# 1_87.net
KiCad netlist of a schematic drawn in EasyEDA Pro
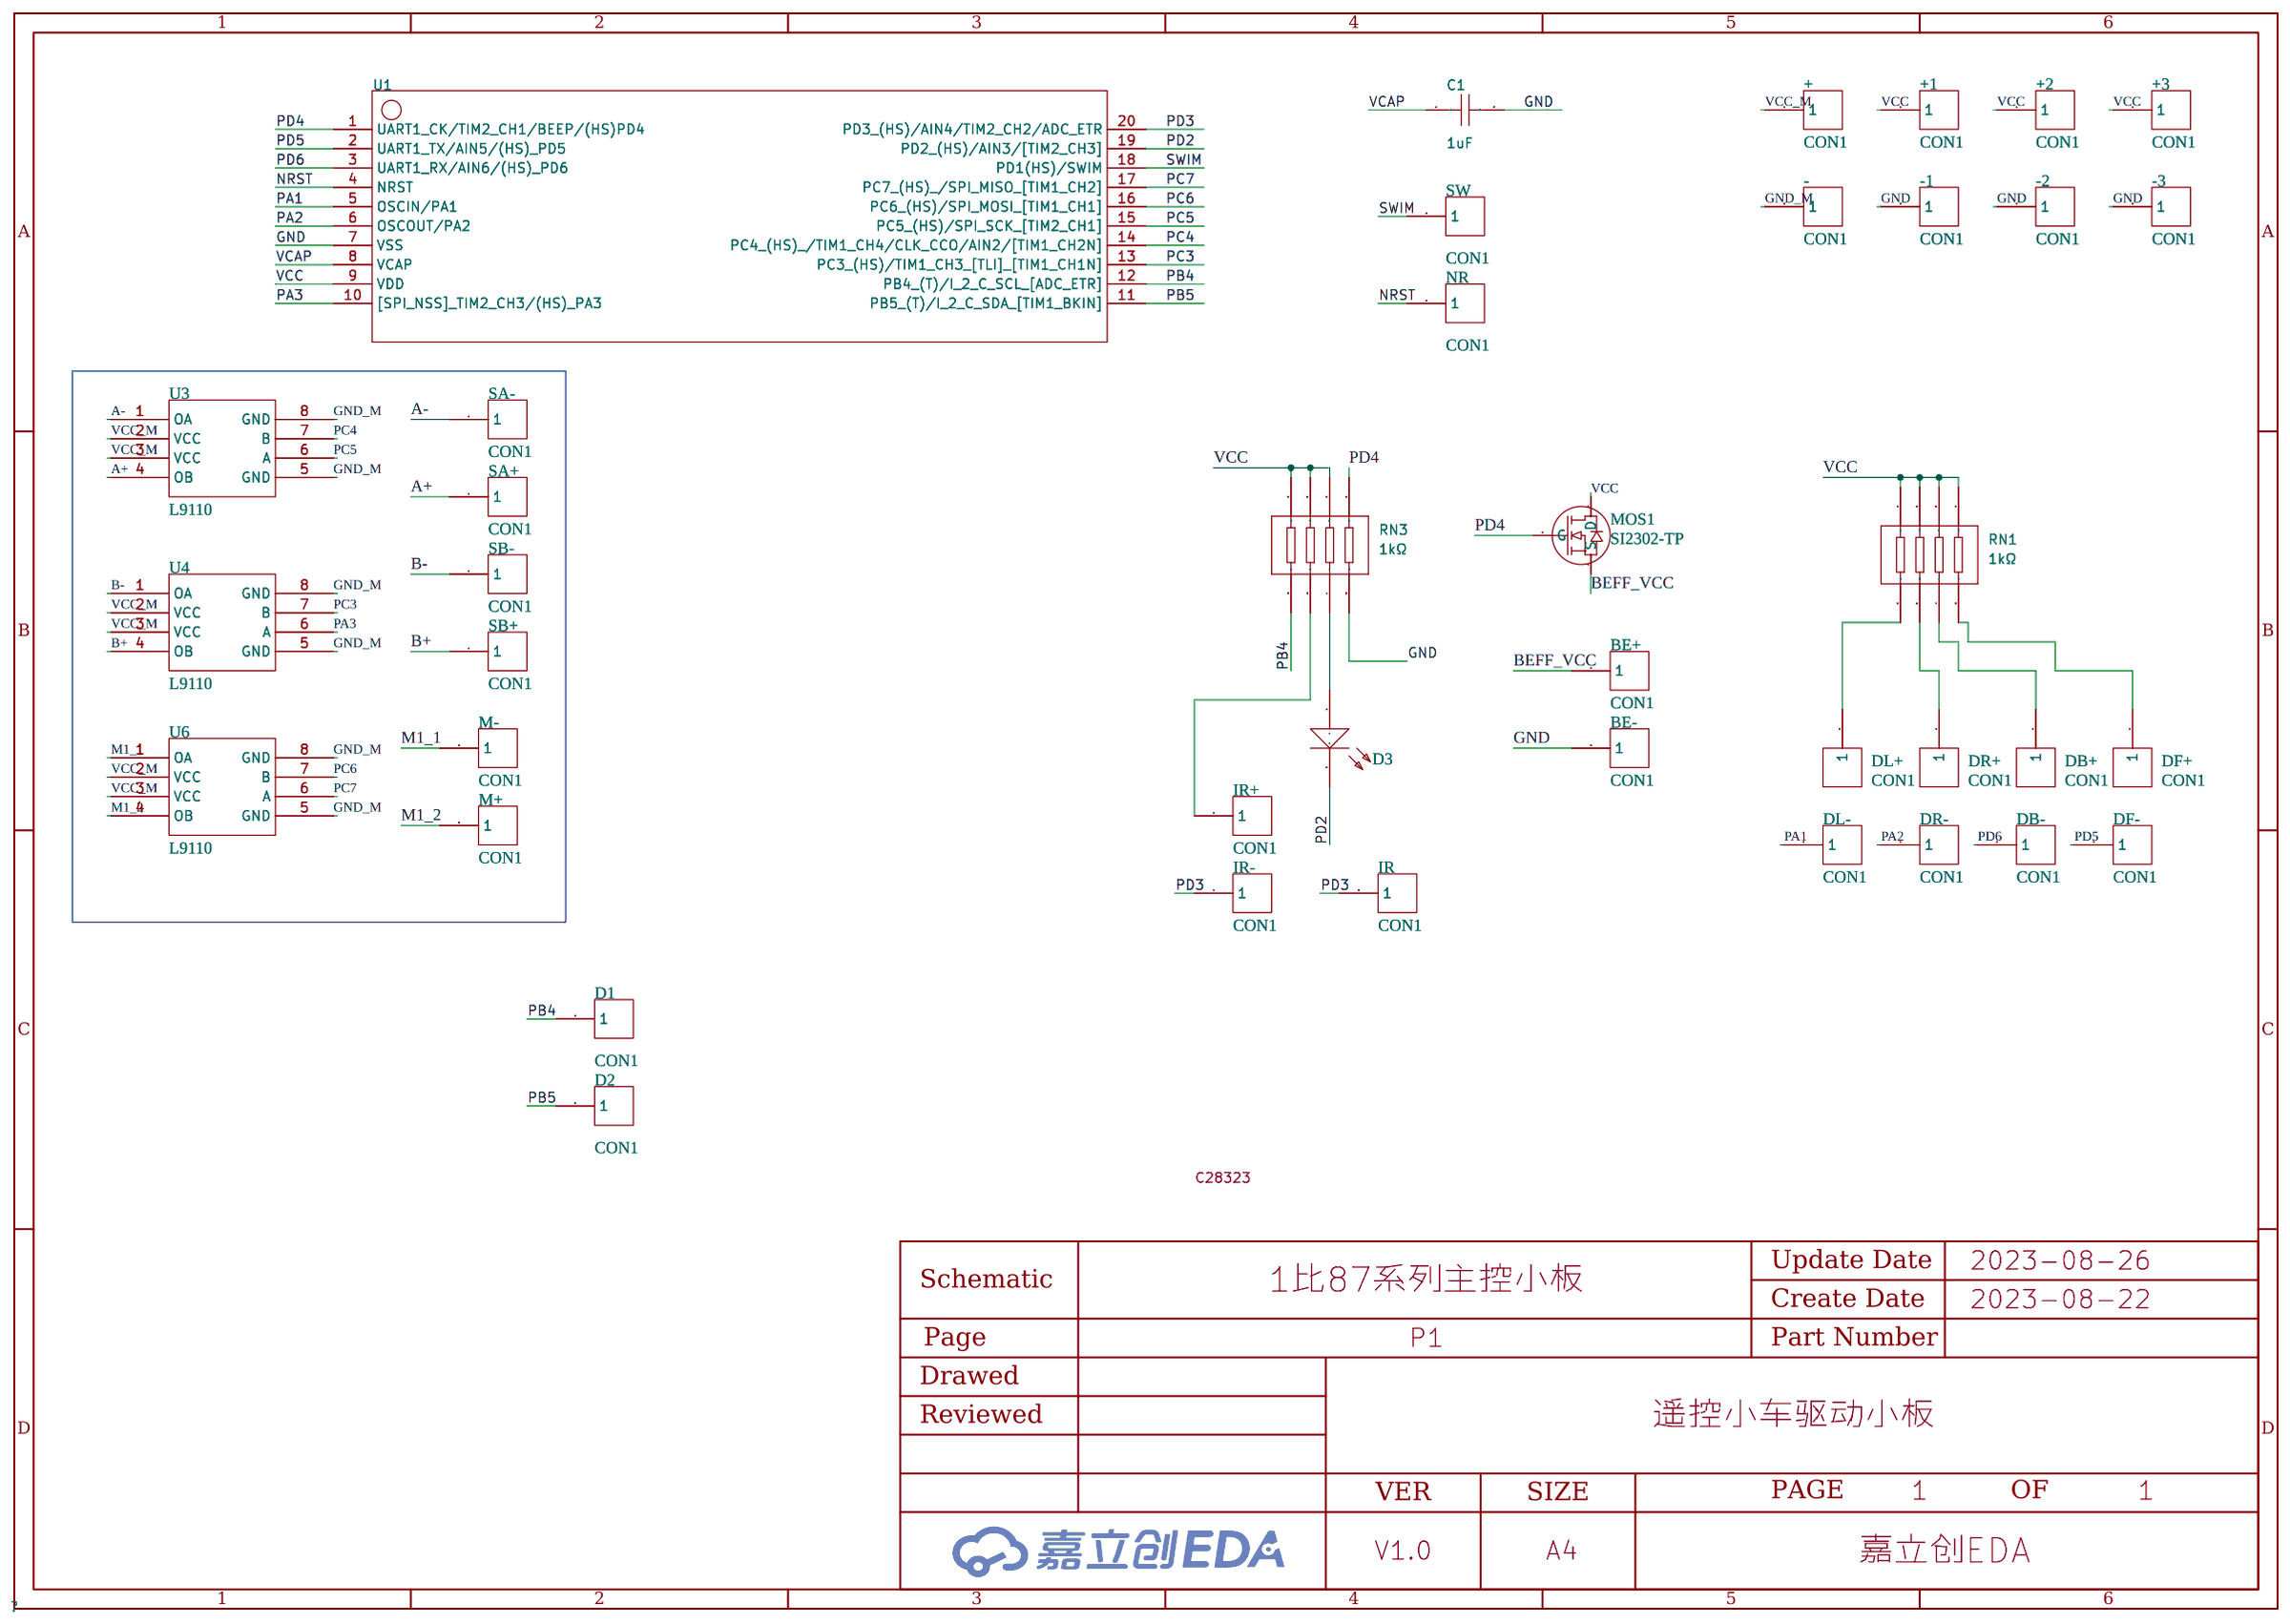
[diagram p0: schematic sheet]

(export (version "E")
  (design (tool "Eeschema 10.0.6"))
  (components
    (comp (ref "+")
      (value "CON1")
      (footprint "easyedapro:CON1_2")
      (libsource (lib "easyedapro") (part "CON1"))
    )
    (comp (ref "+1")
      (value "CON1")
      (footprint "easyedapro:CON1_2")
      (libsource (lib "easyedapro") (part "CON1"))
    )
    (comp (ref "+2")
      (value "CON1")
      (footprint "easyedapro:CON1_2")
      (libsource (lib "easyedapro") (part "CON1"))
    )
    (comp (ref "+3")
      (value "CON1")
      (footprint "easyedapro:CON1_2")
      (libsource (lib "easyedapro") (part "CON1"))
    )
    (comp (ref "-")
      (value "CON1")
      (footprint "easyedapro:CON1_2")
      (libsource (lib "easyedapro") (part "CON1"))
    )
    (comp (ref "-1")
      (value "CON1")
      (footprint "easyedapro:CON1_2")
      (libsource (lib "easyedapro") (part "CON1"))
    )
    (comp (ref "-2")
      (value "CON1")
      (footprint "easyedapro:CON1_2")
      (libsource (lib "easyedapro") (part "CON1"))
    )
    (comp (ref "-3")
      (value "CON1")
      (footprint "easyedapro:CON1_2")
      (libsource (lib "easyedapro") (part "CON1"))
    )
    (comp (ref "BE+")
      (value "CON1")
      (footprint "easyedapro:CON1_2")
      (libsource (lib "easyedapro") (part "CON1"))
    )
    (comp (ref "BE-")
      (value "CON1")
      (footprint "easyedapro:CON1_2")
      (libsource (lib "easyedapro") (part "CON1"))
    )
    (comp (ref "C1")
      (value "1uF")
      (fields
        (field (name "Manufacturer Part") "CL21B105KBFNNNE")
        (field (name "Manufacturer") "SAMSUNG(三星)")
        (field (name "Supplier Part") "C28323")
      )
      (libsource (lib "easyedapro") (part "CapAcitance"))
    )
    (comp (ref "D1")
      (value "CON1")
      (footprint "easyedapro:CON1_2")
      (libsource (lib "easyedapro") (part "CON1"))
    )
    (comp (ref "D2")
      (value "CON1")
      (footprint "easyedapro:CON1_2")
      (libsource (lib "easyedapro") (part "CON1"))
    )
    (comp (ref "D3")
      (value "LED0")
      (footprint "easyedapro:LED-0805")
      (description "发光二极管")
      (fields (field (name "Publisher") "Altium Limited"))
      (libsource (lib "easyedapro") (part "LED0"))
    )
    (comp (ref "DB+")
      (value "CON1")
      (footprint "easyedapro:CON1_2")
      (libsource (lib "easyedapro") (part "CON1"))
    )
    (comp (ref "DB-")
      (value "CON1")
      (footprint "easyedapro:CON1_2")
      (libsource (lib "easyedapro") (part "CON1"))
    )
    (comp (ref "DF+")
      (value "CON1")
      (footprint "easyedapro:CON1_2")
      (libsource (lib "easyedapro") (part "CON1"))
    )
    (comp (ref "DF-")
      (value "CON1")
      (footprint "easyedapro:CON1_2")
      (libsource (lib "easyedapro") (part "CON1"))
    )
    (comp (ref "DL+")
      (value "CON1")
      (footprint "easyedapro:CON1_2")
      (libsource (lib "easyedapro") (part "CON1"))
    )
    (comp (ref "DL-")
      (value "CON1")
      (footprint "easyedapro:CON1_2")
      (libsource (lib "easyedapro") (part "CON1"))
    )
    (comp (ref "DR+")
      (value "CON1")
      (footprint "easyedapro:CON1_2")
      (libsource (lib "easyedapro") (part "CON1"))
    )
    (comp (ref "DR-")
      (value "CON1")
      (footprint "easyedapro:CON1_2")
      (libsource (lib "easyedapro") (part "CON1"))
    )
    (comp (ref "IR")
      (value "CON1")
      (footprint "easyedapro:CON1_2")
      (libsource (lib "easyedapro") (part "CON1"))
    )
    (comp (ref "IR+")
      (value "CON1")
      (footprint "easyedapro:CON1_2")
      (libsource (lib "easyedapro") (part "CON1"))
    )
    (comp (ref "IR-")
      (value "CON1")
      (footprint "easyedapro:CON1_2")
      (libsource (lib "easyedapro") (part "CON1"))
    )
    (comp (ref "M+")
      (value "CON1")
      (footprint "easyedapro:CON1_2")
      (libsource (lib "easyedapro") (part "CON1"))
    )
    (comp (ref "M-")
      (value "CON1")
      (footprint "easyedapro:CON1_2")
      (libsource (lib "easyedapro") (part "CON1"))
    )
    (comp (ref "MOS1")
      (value "SI2302-TP")
      (footprint "easyedapro:SOT-23_MCC")
      (description "No Description Available")
      (fields (field (name "Copyright") "Copyright (C) 2022 Ultra Librarian. All rights reserved."))
      (libsource (lib "easyedapro") (part "SI2302-TP"))
    )
    (comp (ref "NR")
      (value "CON1")
      (footprint "easyedapro:CON1_2")
      (libsource (lib "easyedapro") (part "CON1"))
    )
    (comp (ref "RN1")
      (value "1kΩ")
      (footprint "easyedapro:RES-ARRAY-SMD_0603-8P-L3.2-W1.6-BL")
      (description "阻值:1kΩ;精度:±5%;单个元件功率:62.5mW;电阻器数:4;")
      (fields
        (field (name "Manufacturer Part") "4D03WGJ0102T5E")
        (field (name "Manufacturer") "UNI-ROYAL(厚声)")
      )
      (libsource (lib "easyedapro") (part "4D03WGJ0102T5E"))
    )
    (comp (ref "RN3")
      (value "1kΩ")
      (footprint "easyedapro:RES-ARRAY-SMD_0603-8P-L3.2-W1.6-BL")
      (description "阻值:1kΩ;精度:±5%;单个元件功率:62.5mW;电阻器数:4;")
      (fields
        (field (name "Manufacturer Part") "4D03WGJ0102T5E")
        (field (name "Manufacturer") "UNI-ROYAL(厚声)")
      )
      (libsource (lib "easyedapro") (part "4D03WGJ0102T5E"))
    )
    (comp (ref "SA+")
      (value "CON1")
      (footprint "easyedapro:CON1_2")
      (libsource (lib "easyedapro") (part "CON1"))
    )
    (comp (ref "SA-")
      (value "CON1")
      (footprint "easyedapro:CON1_2")
      (libsource (lib "easyedapro") (part "CON1"))
    )
    (comp (ref "SB+")
      (value "CON1")
      (footprint "easyedapro:CON1_2")
      (libsource (lib "easyedapro") (part "CON1"))
    )
    (comp (ref "SB-")
      (value "CON1")
      (footprint "easyedapro:CON1_2")
      (libsource (lib "easyedapro") (part "CON1"))
    )
    (comp (ref "SW")
      (value "CON1")
      (footprint "easyedapro:CON1_2")
      (libsource (lib "easyedapro") (part "CON1"))
    )
    (comp (ref "U1")
      (value "STM8S003F3P6")
      (footprint "easyedapro:TSSOP-20_L6.5-W4.4-P0.65-LS6.4-BL")
      (description "CPU内核:STM8;CPU最大主频:16MHz;程序存储容量:8KB;程序存储器类型:FLASH;RAM总容量:1KB;GPIO端口数量:16;")
      (fields (field (name "Manufacturer") "ST(意法半导体)"))
      (libsource (lib "easyedapro") (part "STM8S003F3P6"))
    )
    (comp (ref "U3")
      (value "L9110")
      (footprint "easyedapro:SOP8")
      (libsource (lib "easyedapro") (part "L9110"))
    )
    (comp (ref "U4")
      (value "L9110")
      (footprint "easyedapro:SOP8")
      (libsource (lib "easyedapro") (part "L9110"))
    )
    (comp (ref "U6")
      (value "L9110")
      (footprint "easyedapro:SOP8")
      (libsource (lib "easyedapro") (part "L9110"))
    )
  )
  (nets
    (net (code "1") (name "/A+") (class "Default")
      (node (ref "SA+") (pin "1") (pinfunction "1_1") (pintype "input"))
      (node (ref "U3") (pin "4") (pinfunction "OB_4") (pintype "input"))
    )
    (net (code "2") (name "/A-") (class "Default")
      (node (ref "SA-") (pin "1") (pinfunction "1_1") (pintype "input"))
      (node (ref "U3") (pin "1") (pinfunction "OA_1") (pintype "input"))
    )
    (net (code "3") (name "/B+") (class "Default")
      (node (ref "SB+") (pin "1") (pinfunction "1_1") (pintype "input"))
      (node (ref "U4") (pin "4") (pinfunction "OB_4") (pintype "input"))
    )
    (net (code "4") (name "/B-") (class "Default")
      (node (ref "SB-") (pin "1") (pinfunction "1_1") (pintype "input"))
      (node (ref "U4") (pin "1") (pinfunction "OA_1") (pintype "input"))
    )
    (net (code "5") (name "/BEFF_VCC") (class "Default")
      (node (ref "BE+") (pin "1") (pinfunction "1_1") (pintype "input"))
      (node (ref "MOS1") (pin "2") (pinfunction "S_2") (pintype "input"))
    )
    (net (code "6") (name "/GND") (class "Default")
      (node (ref "-1") (pin "1") (pinfunction "1_1") (pintype "input"))
      (node (ref "-2") (pin "1") (pinfunction "1_1") (pintype "input"))
      (node (ref "-3") (pin "1") (pinfunction "1_1") (pintype "input"))
      (node (ref "BE-") (pin "1") (pinfunction "1_1") (pintype "input"))
      (node (ref "C1") (pin "2") (pinfunction "2_2") (pintype "input"))
      (node (ref "RN3") (pin "8") (pinfunction "8_8") (pintype "input"))
      (node (ref "U1") (pin "7") (pinfunction "VSS_7") (pintype "input"))
    )
    (net (code "7") (name "/GND_M") (class "Default")
      (node (ref "-") (pin "1") (pinfunction "1_1") (pintype "input"))
      (node (ref "U3") (pin "5") (pinfunction "GND_5") (pintype "input"))
      (node (ref "U3") (pin "8") (pinfunction "GND_8") (pintype "input"))
      (node (ref "U4") (pin "5") (pinfunction "GND_5") (pintype "input"))
      (node (ref "U4") (pin "8") (pinfunction "GND_8") (pintype "input"))
      (node (ref "U6") (pin "5") (pinfunction "GND_5") (pintype "input"))
      (node (ref "U6") (pin "8") (pinfunction "GND_8") (pintype "input"))
    )
    (net (code "8") (name "/M1_1") (class "Default")
      (node (ref "M-") (pin "1") (pinfunction "1_1") (pintype "input"))
      (node (ref "U6") (pin "1") (pinfunction "OA_1") (pintype "input"))
    )
    (net (code "9") (name "/M1_2") (class "Default")
      (node (ref "M+") (pin "1") (pinfunction "1_1") (pintype "input"))
      (node (ref "U6") (pin "4") (pinfunction "OB_4") (pintype "input"))
    )
    (net (code "10") (name "/NRST") (class "Default")
      (node (ref "NR") (pin "1") (pinfunction "1_1") (pintype "input"))
      (node (ref "U1") (pin "4") (pinfunction "NRST_4") (pintype "input"))
    )
    (net (code "11") (name "/PA1") (class "Default")
      (node (ref "DL-") (pin "1") (pinfunction "1_1") (pintype "input"))
      (node (ref "U1") (pin "5") (pinfunction "OSCIN/PA1_5") (pintype "input"))
    )
    (net (code "12") (name "/PA2") (class "Default")
      (node (ref "DR-") (pin "1") (pinfunction "1_1") (pintype "input"))
      (node (ref "U1") (pin "6") (pinfunction "OSCOUT/PA2_6") (pintype "input"))
    )
    (net (code "13") (name "/PA3") (class "Default")
      (node (ref "U1") (pin "10") (pinfunction "[SPI_NSS]_TIM2_CH3/(HS)_PA3_10") (pintype "input"))
      (node (ref "U4") (pin "6") (pinfunction "A_6") (pintype "input"))
    )
    (net (code "14") (name "/PB4") (class "Default")
      (node (ref "D1") (pin "1") (pinfunction "1_1") (pintype "input"))
      (node (ref "RN3") (pin "5") (pinfunction "5_5") (pintype "input"))
      (node (ref "U1") (pin "12") (pinfunction "PB4_(T)/I_2_C_SCL_[ADC_ETR]_12") (pintype "input"))
    )
    (net (code "15") (name "/PB5") (class "Default")
      (node (ref "D2") (pin "1") (pinfunction "1_1") (pintype "input"))
      (node (ref "U1") (pin "11") (pinfunction "PB5_(T)/I_2_C_SDA_[TIM1_BKIN]_11") (pintype "input"))
    )
    (net (code "16") (name "/PC3") (class "Default")
      (node (ref "U1") (pin "13") (pinfunction "PC3_(HS)/TIM1_CH3_[TLI]_[TIM1_CH1N]_13") (pintype "input"))
      (node (ref "U4") (pin "7") (pinfunction "B_7") (pintype "input"))
    )
    (net (code "17") (name "/PC4") (class "Default")
      (node (ref "U1") (pin "14") (pinfunction "PC4_(HS)_/TIM1_CH4/CLK_CCO/AIN2/[TIM1_CH2N]_14") (pintype "input"))
      (node (ref "U3") (pin "7") (pinfunction "B_7") (pintype "input"))
    )
    (net (code "18") (name "/PC5") (class "Default")
      (node (ref "U1") (pin "15") (pinfunction "PC5_(HS)/SPI_SCK_[TIM2_CH1]_15") (pintype "input"))
      (node (ref "U3") (pin "6") (pinfunction "A_6") (pintype "input"))
    )
    (net (code "19") (name "/PC6") (class "Default")
      (node (ref "U1") (pin "16") (pinfunction "PC6_(HS)/SPI_MOSI_[TIM1_CH1]_16") (pintype "input"))
      (node (ref "U6") (pin "7") (pinfunction "B_7") (pintype "input"))
    )
    (net (code "20") (name "/PC7") (class "Default")
      (node (ref "U1") (pin "17") (pinfunction "PC7_(HS)_/SPI_MISO_[TIM1_CH2]_17") (pintype "input"))
      (node (ref "U6") (pin "6") (pinfunction "A_6") (pintype "input"))
    )
    (net (code "21") (name "/PD2") (class "Default")
      (node (ref "D3") (pin "2") (pinfunction "K_2") (pintype "input"))
      (node (ref "U1") (pin "19") (pinfunction "PD2_(HS)/AIN3/[TIM2_CH3]_19") (pintype "input"))
    )
    (net (code "22") (name "/PD3") (class "Default")
      (node (ref "IR") (pin "1") (pinfunction "1_1") (pintype "input"))
      (node (ref "IR-") (pin "1") (pinfunction "1_1") (pintype "input"))
      (node (ref "U1") (pin "20") (pinfunction "PD3_(HS)/AIN4/TIM2_CH2/ADC_ETR_20") (pintype "input"))
    )
    (net (code "23") (name "/PD4") (class "Default")
      (node (ref "MOS1") (pin "1") (pinfunction "G_1") (pintype "input"))
      (node (ref "RN3") (pin "1") (pinfunction "1_1") (pintype "input"))
      (node (ref "U1") (pin "1") (pinfunction "UART1_CK/TIM2_CH1/BEEP/(HS)PD4_1") (pintype "input"))
    )
    (net (code "24") (name "/PD5") (class "Default")
      (node (ref "DF-") (pin "1") (pinfunction "1_1") (pintype "input"))
      (node (ref "U1") (pin "2") (pinfunction "UART1_TX/AIN5/(HS)_PD5_2") (pintype "input"))
    )
    (net (code "25") (name "/PD6") (class "Default")
      (node (ref "DB-") (pin "1") (pinfunction "1_1") (pintype "input"))
      (node (ref "U1") (pin "3") (pinfunction "UART1_RX/AIN6/(HS)_PD6_3") (pintype "input"))
    )
    (net (code "26") (name "/SWIM") (class "Default")
      (node (ref "SW") (pin "1") (pinfunction "1_1") (pintype "input"))
      (node (ref "U1") (pin "18") (pinfunction "PD1(HS)/SWIM_18") (pintype "input"))
    )
    (net (code "27") (name "/VCAP") (class "Default")
      (node (ref "C1") (pin "1") (pinfunction "1_1") (pintype "input"))
      (node (ref "U1") (pin "8") (pinfunction "VCAP_8") (pintype "input"))
    )
    (net (code "28") (name "/VCC") (class "Default")
      (node (ref "+1") (pin "1") (pinfunction "1_1") (pintype "input"))
      (node (ref "+2") (pin "1") (pinfunction "1_1") (pintype "input"))
      (node (ref "+3") (pin "1") (pinfunction "1_1") (pintype "input"))
      (node (ref "MOS1") (pin "3") (pinfunction "D_3") (pintype "input"))
      (node (ref "RN1") (pin "1") (pinfunction "1_1") (pintype "input"))
      (node (ref "RN1") (pin "2") (pinfunction "2_2") (pintype "input"))
      (node (ref "RN1") (pin "3") (pinfunction "3_3") (pintype "input"))
      (node (ref "RN1") (pin "4") (pinfunction "4_4") (pintype "input"))
      (node (ref "RN3") (pin "2") (pinfunction "2_2") (pintype "input"))
      (node (ref "RN3") (pin "3") (pinfunction "3_3") (pintype "input"))
      (node (ref "RN3") (pin "4") (pinfunction "4_4") (pintype "input"))
      (node (ref "U1") (pin "9") (pinfunction "VDD_9") (pintype "input"))
    )
    (net (code "29") (name "/VCC_M") (class "Default")
      (node (ref "+") (pin "1") (pinfunction "1_1") (pintype "input"))
      (node (ref "U3") (pin "2") (pinfunction "VCC_2") (pintype "input"))
      (node (ref "U3") (pin "3") (pinfunction "VCC_3") (pintype "input"))
      (node (ref "U4") (pin "2") (pinfunction "VCC_2") (pintype "input"))
      (node (ref "U4") (pin "3") (pinfunction "VCC_3") (pintype "input"))
      (node (ref "U6") (pin "2") (pinfunction "VCC_2") (pintype "input"))
      (node (ref "U6") (pin "3") (pinfunction "VCC_3") (pintype "input"))
    )
    (net (code "30") (name "Net-(D3-A)") (class "Default")
      (node (ref "D3") (pin "1") (pinfunction "A_1") (pintype "input"))
      (node (ref "RN3") (pin "7") (pinfunction "7_7") (pintype "input"))
    )
    (net (code "31") (name "Net-(DB+-Pad1)") (class "Default")
      (node (ref "DB+") (pin "1") (pinfunction "1_1") (pintype "input"))
      (node (ref "RN1") (pin "7") (pinfunction "7_7") (pintype "input"))
    )
    (net (code "32") (name "Net-(DF+-Pad1)") (class "Default")
      (node (ref "DF+") (pin "1") (pinfunction "1_1") (pintype "input"))
      (node (ref "RN1") (pin "8") (pinfunction "8_8") (pintype "input"))
    )
    (net (code "33") (name "Net-(DL+-Pad1)") (class "Default")
      (node (ref "DL+") (pin "1") (pinfunction "1_1") (pintype "input"))
      (node (ref "RN1") (pin "5") (pinfunction "5_5") (pintype "input"))
    )
    (net (code "34") (name "Net-(DR+-Pad1)") (class "Default")
      (node (ref "DR+") (pin "1") (pinfunction "1_1") (pintype "input"))
      (node (ref "RN1") (pin "6") (pinfunction "6_6") (pintype "input"))
    )
    (net (code "35") (name "Net-(IR+-Pad1)") (class "Default")
      (node (ref "IR+") (pin "1") (pinfunction "1_1") (pintype "input"))
      (node (ref "RN3") (pin "6") (pinfunction "6_6") (pintype "input"))
    )
  )
)
